# motadora.net
KiCad netlist of a schematic drawn in EAGLE
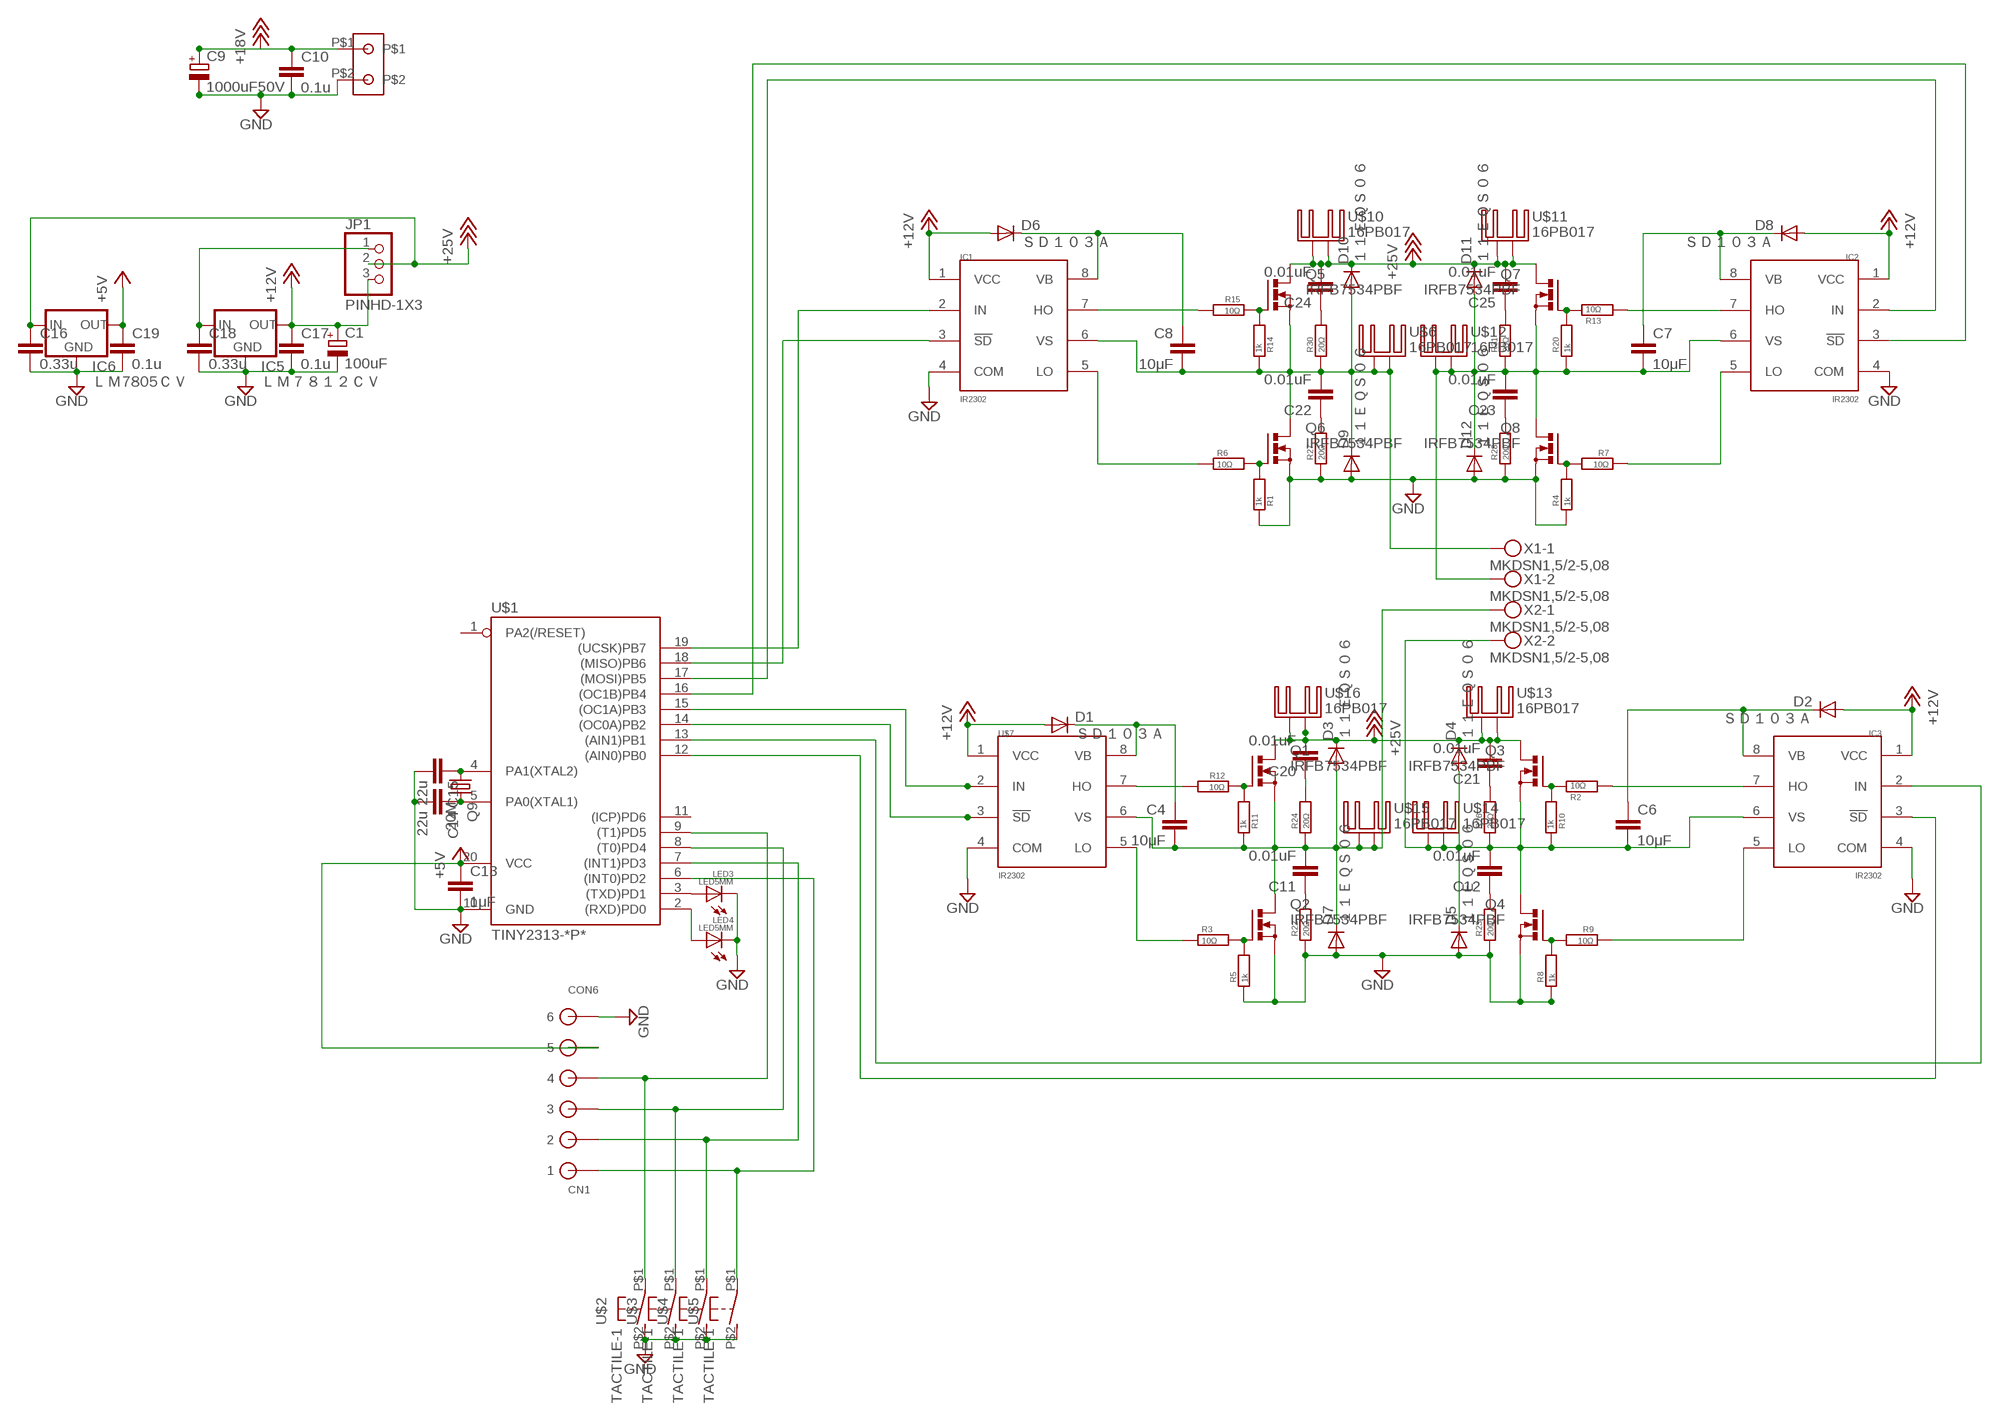
[diagram p0: schematic, sheet 1]

(export (version "E")
  (design (tool "Eeschema 10.0.6"))
  (components
    (comp (ref "C1")
      (value "100uF")
      (footprint "eagle-import:TT2D6")
      (libsource (lib "eagle-import") (part "CPOL-EUTT2D6"))
    )
    (comp (ref "C4")
      (value "10μF")
      (footprint "eagle-import:C025-025X050")
      (libsource (lib "eagle-import") (part "C-EU025-025X050"))
    )
    (comp (ref "C6")
      (value "10μF")
      (footprint "eagle-import:C025-025X050")
      (libsource (lib "eagle-import") (part "C-EU025-025X050"))
    )
    (comp (ref "C7")
      (value "10μF")
      (footprint "eagle-import:C025-025X050")
      (libsource (lib "eagle-import") (part "C-EU025-025X050"))
    )
    (comp (ref "C8")
      (value "10μF")
      (footprint "eagle-import:C025-025X050")
      (libsource (lib "eagle-import") (part "C-EU025-025X050"))
    )
    (comp (ref "C9")
      (value "1000uF50V")
      (footprint "eagle-import:E5-13")
      (libsource (lib "eagle-import") (part "CPOL-EUE5-13"))
    )
    (comp (ref "C10")
      (value "0.1u")
      (footprint "eagle-import:C5B3")
      (libsource (lib "eagle-import") (part "C5/3"))
    )
    (comp (ref "C11")
      (value "0.01uF")
      (footprint "eagle-import:C025-024X044")
      (libsource (lib "eagle-import") (part "_resistor(抵抗)_C-EU025-024X044"))
    )
    (comp (ref "C12")
      (value "0.01uF")
      (footprint "eagle-import:C025-024X044")
      (libsource (lib "eagle-import") (part "_resistor(抵抗)_C-EU025-024X044"))
    )
    (comp (ref "C13")
      (value "1μF")
      (footprint "eagle-import:C050-025X075")
      (libsource (lib "eagle-import") (part "_resistor(抵抗)_C-EU050-025X075"))
    )
    (comp (ref "C14")
      (value "22u")
      (footprint "eagle-import:C025-024X044")
      (libsource (lib "eagle-import") (part "C-EU025-024X044"))
    )
    (comp (ref "C15")
      (value "22u")
      (footprint "eagle-import:C025-024X044")
      (libsource (lib "eagle-import") (part "C-EU025-024X044"))
    )
    (comp (ref "C16")
      (value "0.33u")
      (footprint "eagle-import:C025-025X050")
      (libsource (lib "eagle-import") (part "_resistor(抵抗)_C-EU025-025X050"))
    )
    (comp (ref "C17")
      (value "0.1u")
      (footprint "eagle-import:C025-025X050")
      (libsource (lib "eagle-import") (part "_resistor(抵抗)_C-EU025-025X050"))
    )
    (comp (ref "C18")
      (value "0.33u")
      (footprint "eagle-import:C025-025X050")
      (libsource (lib "eagle-import") (part "_resistor(抵抗)_C-EU025-025X050"))
    )
    (comp (ref "C19")
      (value "0.1u")
      (footprint "eagle-import:C025-025X050")
      (libsource (lib "eagle-import") (part "_resistor(抵抗)_C-EU025-025X050"))
    )
    (comp (ref "C20")
      (value "0.01uF")
      (footprint "eagle-import:C025-024X044")
      (libsource (lib "eagle-import") (part "_resistor(抵抗)_C-EU025-024X044"))
    )
    (comp (ref "C21")
      (value "0.01uF")
      (footprint "eagle-import:C025-024X044")
      (libsource (lib "eagle-import") (part "_resistor(抵抗)_C-EU025-024X044"))
    )
    (comp (ref "C22")
      (value "0.01uF")
      (footprint "eagle-import:C025-024X044")
      (libsource (lib "eagle-import") (part "_resistor(抵抗)_C-EU025-024X044"))
    )
    (comp (ref "C23")
      (value "0.01uF")
      (footprint "eagle-import:C025-024X044")
      (libsource (lib "eagle-import") (part "_resistor(抵抗)_C-EU025-024X044"))
    )
    (comp (ref "C24")
      (value "0.01uF")
      (footprint "eagle-import:C025-024X044")
      (libsource (lib "eagle-import") (part "_resistor(抵抗)_C-EU025-024X044"))
    )
    (comp (ref "C25")
      (value "0.01uF")
      (footprint "eagle-import:C025-024X044")
      (libsource (lib "eagle-import") (part "_resistor(抵抗)_C-EU025-024X044"))
    )
    (comp (ref "CN1")
      (value "CON6")
      (footprint "eagle-import:CON6")
      (libsource (lib "eagle-import") (part "CON6"))
    )
    (comp (ref "D1")
      (value "ＳＤ１０３Ａ")
      (footprint "eagle-import:D-5")
      (libsource (lib "eagle-import") (part "DIODE-D-5"))
    )
    (comp (ref "D2")
      (value "ＳＤ１０３Ａ")
      (footprint "eagle-import:D-5")
      (libsource (lib "eagle-import") (part "DIODE-D-5"))
    )
    (comp (ref "D3")
      (value "１１ＥＱＳ０６")
      (footprint "eagle-import:D-5")
      (libsource (lib "eagle-import") (part "DIODE-D-5"))
    )
    (comp (ref "D4")
      (value "１１ＥＱＳ０６")
      (footprint "eagle-import:D-5")
      (libsource (lib "eagle-import") (part "DIODE-D-5"))
    )
    (comp (ref "D5")
      (value "１１ＥＱＳ０６")
      (footprint "eagle-import:D-5")
      (libsource (lib "eagle-import") (part "DIODE-D-5"))
    )
    (comp (ref "D6")
      (value "ＳＤ１０３Ａ")
      (footprint "eagle-import:D-5")
      (libsource (lib "eagle-import") (part "DIODE-D-5"))
    )
    (comp (ref "D7")
      (value "１１ＥＱＳ０６")
      (footprint "eagle-import:D-5")
      (libsource (lib "eagle-import") (part "DIODE-D-5"))
    )
    (comp (ref "D8")
      (value "ＳＤ１０３Ａ")
      (footprint "eagle-import:D-5")
      (libsource (lib "eagle-import") (part "DIODE-D-5"))
    )
    (comp (ref "D9")
      (value "１１ＥＱＳ０６")
      (footprint "eagle-import:D-5")
      (libsource (lib "eagle-import") (part "DIODE-D-5"))
    )
    (comp (ref "D10")
      (value "１１ＥＱＳ０６")
      (footprint "eagle-import:D-5")
      (libsource (lib "eagle-import") (part "DIODE-D-5"))
    )
    (comp (ref "D11")
      (value "１１ＥＱＳ０６")
      (footprint "eagle-import:D-5")
      (libsource (lib "eagle-import") (part "DIODE-D-5"))
    )
    (comp (ref "D12")
      (value "１１ＥＱＳ０６")
      (footprint "eagle-import:D-5")
      (libsource (lib "eagle-import") (part "DIODE-D-5"))
    )
    (comp (ref "IC1")
      (value "IR2302")
      (footprint "eagle-import:DIL08")
      (libsource (lib "eagle-import") (part "IR2302IR2302"))
    )
    (comp (ref "IC2")
      (value "IR2302")
      (footprint "eagle-import:DIL08")
      (libsource (lib "eagle-import") (part "IR2302IR2302"))
    )
    (comp (ref "IC3")
      (value "IR2302")
      (footprint "eagle-import:DIL08")
      (libsource (lib "eagle-import") (part "IR2302IR2302"))
    )
    (comp (ref "IC5")
      (value "ＬＭ７８１２ＣＶ")
      (footprint "eagle-import:78XXS")
      (libsource (lib "eagle-import") (part "78XXS"))
    )
    (comp (ref "IC6")
      (value "ＬＭ7805ＣＶ")
      (footprint "eagle-import:78XXS")
      (libsource (lib "eagle-import") (part "78XXS"))
    )
    (comp (ref "JP1")
      (value "PINHD-1X3")
      (footprint "eagle-import:1X03")
      (libsource (lib "eagle-import") (part "PINHD-1X3"))
    )
    (comp (ref "LED3")
      (value "LED5MM")
      (footprint "eagle-import:LED5MM")
      (libsource (lib "eagle-import") (part "LED5MM"))
    )
    (comp (ref "LED4")
      (value "LED5MM")
      (footprint "eagle-import:LED5MM")
      (libsource (lib "eagle-import") (part "LED5MM"))
    )
    (comp (ref "Q1")
      (value "IRFB7534PBF")
      (footprint "eagle-import:TO220BV")
      (libsource (lib "eagle-import") (part "BUZ11BV"))
    )
    (comp (ref "Q2")
      (value "IRFB7534PBF")
      (footprint "eagle-import:TO220BV")
      (libsource (lib "eagle-import") (part "BUZ11BV"))
    )
    (comp (ref "Q3")
      (value "IRFB7534PBF")
      (footprint "eagle-import:TO220BV")
      (libsource (lib "eagle-import") (part "BUZ11BV"))
    )
    (comp (ref "Q4")
      (value "IRFB7534PBF")
      (footprint "eagle-import:TO220BV")
      (libsource (lib "eagle-import") (part "BUZ11BV"))
    )
    (comp (ref "Q5")
      (value "IRFB7534PBF")
      (footprint "eagle-import:TO220BV")
      (libsource (lib "eagle-import") (part "BUZ11BV"))
    )
    (comp (ref "Q6")
      (value "IRFB7534PBF")
      (footprint "eagle-import:TO220BV")
      (libsource (lib "eagle-import") (part "BUZ11BV"))
    )
    (comp (ref "Q7")
      (value "IRFB7534PBF")
      (footprint "eagle-import:TO220BV")
      (libsource (lib "eagle-import") (part "BUZ11BV"))
    )
    (comp (ref "Q8")
      (value "IRFB7534PBF")
      (footprint "eagle-import:TO220BV")
      (libsource (lib "eagle-import") (part "BUZ11BV"))
    )
    (comp (ref "Q9")
      (value "20M")
      (footprint "eagle-import:HC49_S")
      (libsource (lib "eagle-import") (part "CRYSTALHC49S"))
    )
    (comp (ref "R1")
      (value "1k")
      (footprint "eagle-import:0207_7")
      (libsource (lib "eagle-import") (part "R-EU_0207/7"))
    )
    (comp (ref "R2")
      (value "10Ω")
      (footprint "eagle-import:1_4W(2.5MM)_")
      (libsource (lib "eagle-import") (part "R-EU_1/4W(2.5MM)"))
    )
    (comp (ref "R3")
      (value "10Ω")
      (footprint "eagle-import:0207_10")
      (libsource (lib "eagle-import") (part "R-EU_0207/10"))
    )
    (comp (ref "R4")
      (value "1k")
      (footprint "eagle-import:0207_7")
      (libsource (lib "eagle-import") (part "R-EU_0207/7"))
    )
    (comp (ref "R5")
      (value "1k")
      (footprint "eagle-import:0207_7")
      (libsource (lib "eagle-import") (part "R-EU_0207/7"))
    )
    (comp (ref "R6")
      (value "10Ω")
      (footprint "eagle-import:0207_10")
      (libsource (lib "eagle-import") (part "R-EU_0207/10"))
    )
    (comp (ref "R7")
      (value "10Ω")
      (footprint "eagle-import:0207_10")
      (libsource (lib "eagle-import") (part "R-EU_0207/10"))
    )
    (comp (ref "R8")
      (value "1k")
      (footprint "eagle-import:0207_7")
      (libsource (lib "eagle-import") (part "R-EU_0207/7"))
    )
    (comp (ref "R9")
      (value "10Ω")
      (footprint "eagle-import:0207_10")
      (libsource (lib "eagle-import") (part "R-EU_0207/10"))
    )
    (comp (ref "R10")
      (value "1k")
      (footprint "eagle-import:1_4W(2.5MM)_")
      (libsource (lib "eagle-import") (part "R-EU_1/4W(2.5MM)"))
    )
    (comp (ref "R11")
      (value "1k")
      (footprint "eagle-import:1_4W(2.5MM)_")
      (libsource (lib "eagle-import") (part "R-EU_1/4W(2.5MM)"))
    )
    (comp (ref "R12")
      (value "10Ω")
      (footprint "eagle-import:1_4W(2.5MM)_")
      (libsource (lib "eagle-import") (part "R-EU_1/4W(2.5MM)"))
    )
    (comp (ref "R13")
      (value "10Ω")
      (footprint "eagle-import:1_4W(2.5MM)_")
      (libsource (lib "eagle-import") (part "R-EU_1/4W(2.5MM)"))
    )
    (comp (ref "R14")
      (value "1k")
      (footprint "eagle-import:1_4W(2.5MM)_")
      (libsource (lib "eagle-import") (part "R-EU_1/4W(2.5MM)"))
    )
    (comp (ref "R15")
      (value "10Ω")
      (footprint "eagle-import:1_4W(2.5MM)_")
      (libsource (lib "eagle-import") (part "R-EU_1/4W(2.5MM)"))
    )
    (comp (ref "R20")
      (value "1k")
      (footprint "eagle-import:1_4W(2.5MM)_")
      (libsource (lib "eagle-import") (part "R-EU_1/4W(2.5MM)"))
    )
    (comp (ref "R22")
      (value "20Ω")
      (footprint "eagle-import:0207_2V")
      (libsource (lib "eagle-import") (part "R-EU_0207/2V"))
    )
    (comp (ref "R23")
      (value "20Ω")
      (footprint "eagle-import:0207_2V")
      (libsource (lib "eagle-import") (part "R-EU_0207/2V"))
    )
    (comp (ref "R24")
      (value "20Ω")
      (footprint "eagle-import:0207_2V")
      (libsource (lib "eagle-import") (part "R-EU_0207/2V"))
    )
    (comp (ref "R26")
      (value "20Ω")
      (footprint "eagle-import:0207_2V")
      (libsource (lib "eagle-import") (part "R-EU_0207/2V"))
    )
    (comp (ref "R27")
      (value "20Ω")
      (footprint "eagle-import:0207_2V")
      (libsource (lib "eagle-import") (part "R-EU_0207/2V"))
    )
    (comp (ref "R28")
      (value "20Ω")
      (footprint "eagle-import:0207_2V")
      (libsource (lib "eagle-import") (part "R-EU_0207/2V"))
    )
    (comp (ref "R30")
      (value "20Ω")
      (footprint "eagle-import:1_4W(2.5MM)_")
      (libsource (lib "eagle-import") (part "R-EU_1/4W(2.5MM)"))
    )
    (comp (ref "R31")
      (value "20Ω")
      (footprint "eagle-import:0207_2V")
      (libsource (lib "eagle-import") (part "R-EU_0207/2V"))
    )
    (comp (ref "T2")
      (value "TANSIDAI")
      (footprint "eagle-import:A")
      (libsource (lib "eagle-import") (part "TANSIDAI"))
    )
    (comp (ref "U$1")
      (value "TINY2313-*P*")
      (footprint "eagle-import:DIL20")
      (libsource (lib "eagle-import") (part "TINY2313-P"))
    )
    (comp (ref "U$2")
      (value "TACTILE-1")
      (footprint "eagle-import:TACTILE")
      (libsource (lib "eagle-import") (part "TACTILE-1"))
    )
    (comp (ref "U$3")
      (value "TACTILE-1")
      (footprint "eagle-import:TACTILE")
      (libsource (lib "eagle-import") (part "TACTILE-1"))
    )
    (comp (ref "U$4")
      (value "TACTILE-1")
      (footprint "eagle-import:TACTILE")
      (libsource (lib "eagle-import") (part "TACTILE-1"))
    )
    (comp (ref "U$5")
      (value "TACTILE-1")
      (footprint "eagle-import:TACTILE")
      (libsource (lib "eagle-import") (part "TACTILE-1"))
    )
    (comp (ref "U$6")
      (value "16PB017")
      (footprint "eagle-import:16PB017")
      (libsource (lib "eagle-import") (part "16PB017"))
    )
    (comp (ref "U$7")
      (value "IR2302")
      (footprint "eagle-import:DIL08")
      (libsource (lib "eagle-import") (part "IR2302IR2302"))
    )
    (comp (ref "U$10")
      (value "16PB017")
      (footprint "eagle-import:16PB017")
      (libsource (lib "eagle-import") (part "16PB017"))
    )
    (comp (ref "U$11")
      (value "16PB017")
      (footprint "eagle-import:16PB017")
      (libsource (lib "eagle-import") (part "16PB017"))
    )
    (comp (ref "U$12")
      (value "16PB017")
      (footprint "eagle-import:16PB017")
      (libsource (lib "eagle-import") (part "16PB017"))
    )
    (comp (ref "U$13")
      (value "16PB017")
      (footprint "eagle-import:16PB017")
      (libsource (lib "eagle-import") (part "16PB017"))
    )
    (comp (ref "U$14")
      (value "16PB017")
      (footprint "eagle-import:16PB017")
      (libsource (lib "eagle-import") (part "16PB017"))
    )
    (comp (ref "U$15")
      (value "16PB017")
      (footprint "eagle-import:16PB017")
      (libsource (lib "eagle-import") (part "16PB017"))
    )
    (comp (ref "U$16")
      (value "16PB017")
      (footprint "eagle-import:16PB017")
      (libsource (lib "eagle-import") (part "16PB017"))
    )
    (comp (ref "X1")
      (value "MKDSN1,5/2-5,08")
      (footprint "eagle-import:MKDSN1,5_2-5,08")
      (fields (field (name "MPN") "MKDSN 1,5/2-5.08"))
      (libsource (lib "eagle-import") (part "MKDSN1,5/2-5,08"))
    )
    (comp (ref "X2")
      (value "MKDSN1,5/2-5,08")
      (footprint "eagle-import:MKDSN1,5_2-5,08")
      (fields (field (name "MPN") "MKDSN 1,5/2-5.08"))
      (libsource (lib "eagle-import") (part "MKDSN1,5/2-5,08"))
    )
  )
  (nets
    (net (code "1") (name "+5V") (class "Default")
      (node (ref "C13") (pin "1") (pinfunction "1_1") (pintype "passive"))
      (node (ref "C19") (pin "1") (pinfunction "1_1") (pintype "passive"))
      (node (ref "CN1") (pin "P$5") (pinfunction "5_P$5") (pintype "bidirectional"))
      (node (ref "IC6") (pin "OUT") (pinfunction "OUT_OUT") (pintype "passive"))
      (node (ref "U$1") (pin "20") (pinfunction "VCC_20") (pintype "power_in"))
    )
    (net (code "2") (name "+12V") (class "Default")
      (node (ref "C1") (pin "+") (pinfunction "+_+") (pintype "passive"))
      (node (ref "C17") (pin "1") (pinfunction "1_1") (pintype "passive"))
      (node (ref "D1") (pin "A") (pinfunction "A_A") (pintype "passive"))
      (node (ref "D2") (pin "A") (pinfunction "A_A") (pintype "passive"))
      (node (ref "D6") (pin "A") (pinfunction "A_A") (pintype "passive"))
      (node (ref "D8") (pin "A") (pinfunction "A_A") (pintype "passive"))
      (node (ref "IC1") (pin "1") (pinfunction "VCC_1") (pintype "bidirectional"))
      (node (ref "IC2") (pin "1") (pinfunction "VCC_1") (pintype "bidirectional"))
      (node (ref "IC3") (pin "1") (pinfunction "VCC_1") (pintype "bidirectional"))
      (node (ref "IC5") (pin "OUT") (pinfunction "OUT_OUT") (pintype "passive"))
      (node (ref "JP1") (pin "3") (pinfunction "3_3") (pintype "passive"))
      (node (ref "U$7") (pin "1") (pinfunction "VCC_1") (pintype "bidirectional"))
    )
    (net (code "3") (name "+18V") (class "Default")
      (node (ref "C10") (pin "1") (pinfunction "1_1") (pintype "passive"))
      (node (ref "C16") (pin "1") (pinfunction "1_1") (pintype "passive"))
      (node (ref "C20") (pin "2") (pinfunction "2_2") (pintype "passive"))
      (node (ref "C21") (pin "2") (pinfunction "2_2") (pintype "passive"))
      (node (ref "C24") (pin "2") (pinfunction "2_2") (pintype "passive"))
      (node (ref "C25") (pin "2") (pinfunction "2_2") (pintype "passive"))
      (node (ref "C9") (pin "+") (pinfunction "+_+") (pintype "passive"))
      (node (ref "D10") (pin "C") (pinfunction "C_C") (pintype "passive"))
      (node (ref "D11") (pin "C") (pinfunction "C_C") (pintype "passive"))
      (node (ref "D3") (pin "C") (pinfunction "C_C") (pintype "passive"))
      (node (ref "D4") (pin "C") (pinfunction "C_C") (pintype "passive"))
      (node (ref "IC6") (pin "IN") (pinfunction "IN_IN") (pintype "input"))
      (node (ref "JP1") (pin "2") (pinfunction "2_2") (pintype "passive"))
      (node (ref "Q1") (pin "D") (pinfunction "D_D") (pintype "passive"))
      (node (ref "Q3") (pin "D") (pinfunction "D_D") (pintype "passive"))
      (node (ref "Q5") (pin "D") (pinfunction "D_D") (pintype "passive"))
      (node (ref "Q7") (pin "D") (pinfunction "D_D") (pintype "passive"))
      (node (ref "T2") (pin "P$1") (pinfunction "P$1_P$1") (pintype "bidirectional"))
      (node (ref "U$10") (pin "P$1") (pinfunction "K_P$1") (pintype "passive"))
      (node (ref "U$10") (pin "P$2") (pinfunction "K_P$2") (pintype "passive"))
      (node (ref "U$11") (pin "P$1") (pinfunction "K_P$1") (pintype "passive"))
      (node (ref "U$11") (pin "P$2") (pinfunction "K_P$2") (pintype "passive"))
      (node (ref "U$13") (pin "P$1") (pinfunction "K_P$1") (pintype "passive"))
      (node (ref "U$13") (pin "P$2") (pinfunction "K_P$2") (pintype "passive"))
      (node (ref "U$16") (pin "P$1") (pinfunction "K_P$1") (pintype "passive"))
      (node (ref "U$16") (pin "P$2") (pinfunction "K_P$2") (pintype "passive"))
    )
    (net (code "4") (name "GND") (class "Default")
      (node (ref "C1") (pin "-") (pinfunction "-_-") (pintype "passive"))
      (node (ref "C10") (pin "2") (pinfunction "2_2") (pintype "passive"))
      (node (ref "C13") (pin "2") (pinfunction "2_2") (pintype "passive"))
      (node (ref "C14") (pin "2") (pinfunction "2_2") (pintype "passive"))
      (node (ref "C15") (pin "2") (pinfunction "2_2") (pintype "passive"))
      (node (ref "C16") (pin "2") (pinfunction "2_2") (pintype "passive"))
      (node (ref "C17") (pin "2") (pinfunction "2_2") (pintype "passive"))
      (node (ref "C18") (pin "2") (pinfunction "2_2") (pintype "passive"))
      (node (ref "C19") (pin "2") (pinfunction "2_2") (pintype "passive"))
      (node (ref "C9") (pin "-") (pinfunction "-_-") (pintype "passive"))
      (node (ref "CN1") (pin "P$6") (pinfunction "6_P$6") (pintype "bidirectional"))
      (node (ref "D12") (pin "A") (pinfunction "A_A") (pintype "passive"))
      (node (ref "D5") (pin "A") (pinfunction "A_A") (pintype "passive"))
      (node (ref "D7") (pin "A") (pinfunction "A_A") (pintype "passive"))
      (node (ref "D9") (pin "A") (pinfunction "A_A") (pintype "passive"))
      (node (ref "IC1") (pin "4") (pinfunction "COM_4") (pintype "bidirectional"))
      (node (ref "IC2") (pin "4") (pinfunction "COM_4") (pintype "bidirectional"))
      (node (ref "IC3") (pin "4") (pinfunction "COM_4") (pintype "bidirectional"))
      (node (ref "IC5") (pin "GND") (pinfunction "GND_GND") (pintype "input"))
      (node (ref "IC6") (pin "GND") (pinfunction "GND_GND") (pintype "input"))
      (node (ref "LED3") (pin "K") (pinfunction "C_K") (pintype "passive"))
      (node (ref "LED4") (pin "K") (pinfunction "C_K") (pintype "passive"))
      (node (ref "Q2") (pin "S") (pinfunction "S_S") (pintype "passive"))
      (node (ref "Q4") (pin "S") (pinfunction "S_S") (pintype "passive"))
      (node (ref "Q6") (pin "S") (pinfunction "S_S") (pintype "passive"))
      (node (ref "Q8") (pin "S") (pinfunction "S_S") (pintype "passive"))
      (node (ref "R1") (pin "1") (pinfunction "1_1") (pintype "passive"))
      (node (ref "R22") (pin "1") (pinfunction "1_1") (pintype "passive"))
      (node (ref "R23") (pin "1") (pinfunction "1_1") (pintype "passive"))
      (node (ref "R27") (pin "1") (pinfunction "1_1") (pintype "passive"))
      (node (ref "R28") (pin "1") (pinfunction "1_1") (pintype "passive"))
      (node (ref "R4") (pin "1") (pinfunction "1_1") (pintype "passive"))
      (node (ref "R5") (pin "1") (pinfunction "1_1") (pintype "passive"))
      (node (ref "R8") (pin "1") (pinfunction "1_1") (pintype "passive"))
      (node (ref "T2") (pin "P$2") (pinfunction "P$2_P$2") (pintype "bidirectional"))
      (node (ref "U$1") (pin "10") (pinfunction "GND_10") (pintype "power_in"))
      (node (ref "U$2") (pin "P$2") (pinfunction "S_P$2") (pintype "passive"))
      (node (ref "U$3") (pin "P$2") (pinfunction "S_P$2") (pintype "passive"))
      (node (ref "U$4") (pin "P$2") (pinfunction "S_P$2") (pintype "passive"))
      (node (ref "U$5") (pin "P$2") (pinfunction "S_P$2") (pintype "passive"))
      (node (ref "U$7") (pin "4") (pinfunction "COM_4") (pintype "bidirectional"))
    )
    (net (code "5") (name "Net-(C11-Pad1)") (class "Default")
      (node (ref "C11") (pin "1") (pinfunction "1_1") (pintype "passive"))
      (node (ref "R22") (pin "2") (pinfunction "2_2") (pintype "passive"))
    )
    (net (code "6") (name "Net-(C12-Pad1)") (class "Default")
      (node (ref "C12") (pin "1") (pinfunction "1_1") (pintype "passive"))
      (node (ref "R23") (pin "2") (pinfunction "2_2") (pintype "passive"))
    )
    (net (code "7") (name "Net-(C18-Pad1)") (class "Default")
      (node (ref "C18") (pin "1") (pinfunction "1_1") (pintype "passive"))
      (node (ref "IC5") (pin "IN") (pinfunction "IN_IN") (pintype "input"))
      (node (ref "JP1") (pin "1") (pinfunction "1_1") (pintype "passive"))
    )
    (net (code "8") (name "Net-(C20-Pad1)") (class "Default")
      (node (ref "C20") (pin "1") (pinfunction "1_1") (pintype "passive"))
      (node (ref "R24") (pin "2") (pinfunction "2_2") (pintype "passive"))
    )
    (net (code "9") (name "Net-(C21-Pad1)") (class "Default")
      (node (ref "C21") (pin "1") (pinfunction "1_1") (pintype "passive"))
      (node (ref "R26") (pin "2") (pinfunction "2_2") (pintype "passive"))
    )
    (net (code "10") (name "Net-(C22-Pad1)") (class "Default")
      (node (ref "C22") (pin "1") (pinfunction "1_1") (pintype "passive"))
      (node (ref "R27") (pin "2") (pinfunction "2_2") (pintype "passive"))
    )
    (net (code "11") (name "Net-(C23-Pad1)") (class "Default")
      (node (ref "C23") (pin "1") (pinfunction "1_1") (pintype "passive"))
      (node (ref "R28") (pin "2") (pinfunction "2_2") (pintype "passive"))
    )
    (net (code "12") (name "Net-(C25-Pad1)") (class "Default")
      (node (ref "C25") (pin "1") (pinfunction "1_1") (pintype "passive"))
      (node (ref "R31") (pin "2") (pinfunction "2_2") (pintype "passive"))
    )
    (net (code "13") (name "Net-(CN1-1)") (class "Default")
      (node (ref "CN1") (pin "P$1") (pinfunction "1_P$1") (pintype "bidirectional"))
      (node (ref "U$1") (pin "6") (pinfunction "(INT0)PD2_6") (pintype "bidirectional"))
      (node (ref "U$5") (pin "P$1") (pinfunction "P_P$1") (pintype "passive"))
    )
    (net (code "14") (name "Net-(CN1-2)") (class "Default")
      (node (ref "CN1") (pin "P$2") (pinfunction "2_P$2") (pintype "bidirectional"))
      (node (ref "U$1") (pin "7") (pinfunction "(INT1)PD3_7") (pintype "bidirectional"))
      (node (ref "U$4") (pin "P$1") (pinfunction "P_P$1") (pintype "passive"))
    )
    (net (code "15") (name "Net-(CN1-3)") (class "Default")
      (node (ref "CN1") (pin "P$3") (pinfunction "3_P$3") (pintype "bidirectional"))
      (node (ref "U$1") (pin "8") (pinfunction "(T0)PD4_8") (pintype "bidirectional"))
      (node (ref "U$3") (pin "P$1") (pinfunction "P_P$1") (pintype "passive"))
    )
    (net (code "16") (name "Net-(CN1-4)") (class "Default")
      (node (ref "CN1") (pin "P$4") (pinfunction "4_P$4") (pintype "bidirectional"))
      (node (ref "U$1") (pin "9") (pinfunction "(T1)PD5_9") (pintype "bidirectional"))
      (node (ref "U$2") (pin "P$1") (pinfunction "P_P$1") (pintype "passive"))
    )
    (net (code "17") (name "Net-(IC1-HO)") (class "Default")
      (node (ref "IC1") (pin "7") (pinfunction "HO_7") (pintype "bidirectional"))
      (node (ref "R15") (pin "4") (pinfunction "2_4") (pintype "passive"))
    )
    (net (code "18") (name "Net-(IC1-IN)") (class "Default")
      (node (ref "IC1") (pin "2") (pinfunction "IN_2") (pintype "bidirectional"))
      (node (ref "U$1") (pin "19") (pinfunction "(UCSK)PB7_19") (pintype "bidirectional"))
    )
    (net (code "19") (name "Net-(IC1-LO)") (class "Default")
      (node (ref "IC1") (pin "5") (pinfunction "LO_5") (pintype "bidirectional"))
      (node (ref "R6") (pin "1") (pinfunction "1_1") (pintype "passive"))
    )
    (net (code "20") (name "Net-(IC1-VB)") (class "Default")
      (node (ref "C8") (pin "1") (pinfunction "1_1") (pintype "passive"))
      (node (ref "D6") (pin "C") (pinfunction "C_C") (pintype "passive"))
      (node (ref "IC1") (pin "8") (pinfunction "VB_8") (pintype "bidirectional"))
    )
    (net (code "21") (name "Net-(IC1-VS)") (class "Default")
      (node (ref "C22") (pin "2") (pinfunction "2_2") (pintype "passive"))
      (node (ref "C8") (pin "2") (pinfunction "2_2") (pintype "passive"))
      (node (ref "D10") (pin "A") (pinfunction "A_A") (pintype "passive"))
      (node (ref "D9") (pin "C") (pinfunction "C_C") (pintype "passive"))
      (node (ref "IC1") (pin "6") (pinfunction "VS_6") (pintype "bidirectional"))
      (node (ref "Q5") (pin "S") (pinfunction "S_S") (pintype "passive"))
      (node (ref "Q6") (pin "D") (pinfunction "D_D") (pintype "passive"))
      (node (ref "R14") (pin "3") (pinfunction "1_3") (pintype "passive"))
      (node (ref "R30") (pin "3") (pinfunction "1_3") (pintype "passive"))
      (node (ref "U$6") (pin "P$1") (pinfunction "K_P$1") (pintype "passive"))
      (node (ref "U$6") (pin "P$2") (pinfunction "K_P$2") (pintype "passive"))
      (node (ref "X1") (pin "1") (pinfunction "KL_1") (pintype "passive"))
    )
    (net (code "22") (name "Net-(IC1-~{SD})") (class "Default")
      (node (ref "IC1") (pin "3") (pinfunction "~{SD}_3") (pintype "bidirectional"))
      (node (ref "U$1") (pin "18") (pinfunction "(MISO)PB6_18") (pintype "bidirectional"))
    )
    (net (code "23") (name "Net-(IC2-HO)") (class "Default")
      (node (ref "IC2") (pin "7") (pinfunction "HO_7") (pintype "bidirectional"))
      (node (ref "R13") (pin "4") (pinfunction "2_4") (pintype "passive"))
    )
    (net (code "24") (name "Net-(IC2-IN)") (class "Default")
      (node (ref "IC2") (pin "2") (pinfunction "IN_2") (pintype "bidirectional"))
      (node (ref "U$1") (pin "17") (pinfunction "(MOSI)PB5_17") (pintype "bidirectional"))
    )
    (net (code "25") (name "Net-(IC2-LO)") (class "Default")
      (node (ref "IC2") (pin "5") (pinfunction "LO_5") (pintype "bidirectional"))
      (node (ref "R7") (pin "1") (pinfunction "1_1") (pintype "passive"))
    )
    (net (code "26") (name "Net-(IC2-VB)") (class "Default")
      (node (ref "C7") (pin "1") (pinfunction "1_1") (pintype "passive"))
      (node (ref "D8") (pin "C") (pinfunction "C_C") (pintype "passive"))
      (node (ref "IC2") (pin "8") (pinfunction "VB_8") (pintype "bidirectional"))
    )
    (net (code "27") (name "Net-(IC2-VS)") (class "Default")
      (node (ref "C23") (pin "2") (pinfunction "2_2") (pintype "passive"))
      (node (ref "C7") (pin "2") (pinfunction "2_2") (pintype "passive"))
      (node (ref "D11") (pin "A") (pinfunction "A_A") (pintype "passive"))
      (node (ref "D12") (pin "C") (pinfunction "C_C") (pintype "passive"))
      (node (ref "IC2") (pin "6") (pinfunction "VS_6") (pintype "bidirectional"))
      (node (ref "Q7") (pin "S") (pinfunction "S_S") (pintype "passive"))
      (node (ref "Q8") (pin "D") (pinfunction "D_D") (pintype "passive"))
      (node (ref "R20") (pin "3") (pinfunction "1_3") (pintype "passive"))
      (node (ref "R31") (pin "1") (pinfunction "1_1") (pintype "passive"))
      (node (ref "U$12") (pin "P$1") (pinfunction "K_P$1") (pintype "passive"))
      (node (ref "U$12") (pin "P$2") (pinfunction "K_P$2") (pintype "passive"))
      (node (ref "X1") (pin "2") (pinfunction "KL_2") (pintype "passive"))
    )
    (net (code "28") (name "Net-(IC2-~{SD})") (class "Default")
      (node (ref "IC2") (pin "3") (pinfunction "~{SD}_3") (pintype "bidirectional"))
      (node (ref "U$1") (pin "16") (pinfunction "(OC1B)PB4_16") (pintype "bidirectional"))
    )
    (net (code "29") (name "Net-(IC3-HO)") (class "Default")
      (node (ref "IC3") (pin "7") (pinfunction "HO_7") (pintype "bidirectional"))
      (node (ref "R2") (pin "4") (pinfunction "2_4") (pintype "passive"))
    )
    (net (code "30") (name "Net-(IC3-IN)") (class "Default")
      (node (ref "IC3") (pin "2") (pinfunction "IN_2") (pintype "bidirectional"))
      (node (ref "U$1") (pin "13") (pinfunction "(AIN1)PB1_13") (pintype "bidirectional"))
    )
    (net (code "31") (name "Net-(IC3-LO)") (class "Default")
      (node (ref "IC3") (pin "5") (pinfunction "LO_5") (pintype "bidirectional"))
      (node (ref "R9") (pin "1") (pinfunction "1_1") (pintype "passive"))
    )
    (net (code "32") (name "Net-(IC3-VB)") (class "Default")
      (node (ref "C6") (pin "1") (pinfunction "1_1") (pintype "passive"))
      (node (ref "D2") (pin "C") (pinfunction "C_C") (pintype "passive"))
      (node (ref "IC3") (pin "8") (pinfunction "VB_8") (pintype "bidirectional"))
    )
    (net (code "33") (name "Net-(IC3-VS)") (class "Default")
      (node (ref "C12") (pin "2") (pinfunction "2_2") (pintype "passive"))
      (node (ref "C6") (pin "2") (pinfunction "2_2") (pintype "passive"))
      (node (ref "D4") (pin "A") (pinfunction "A_A") (pintype "passive"))
      (node (ref "D5") (pin "C") (pinfunction "C_C") (pintype "passive"))
      (node (ref "IC3") (pin "6") (pinfunction "VS_6") (pintype "bidirectional"))
      (node (ref "Q3") (pin "S") (pinfunction "S_S") (pintype "passive"))
      (node (ref "Q4") (pin "D") (pinfunction "D_D") (pintype "passive"))
      (node (ref "R10") (pin "3") (pinfunction "1_3") (pintype "passive"))
      (node (ref "R26") (pin "1") (pinfunction "1_1") (pintype "passive"))
      (node (ref "U$14") (pin "P$1") (pinfunction "K_P$1") (pintype "passive"))
      (node (ref "U$14") (pin "P$2") (pinfunction "K_P$2") (pintype "passive"))
      (node (ref "X2") (pin "2") (pinfunction "KL_2") (pintype "passive"))
    )
    (net (code "34") (name "Net-(IC3-~{SD})") (class "Default")
      (node (ref "IC3") (pin "3") (pinfunction "~{SD}_3") (pintype "bidirectional"))
      (node (ref "U$1") (pin "12") (pinfunction "(AIN0)PB0_12") (pintype "bidirectional"))
    )
    (net (code "35") (name "Net-(Q2-PadG)") (class "Default")
      (node (ref "Q2") (pin "G") (pinfunction "G_G") (pintype "passive"))
      (node (ref "R3") (pin "2") (pinfunction "2_2") (pintype "passive"))
      (node (ref "R5") (pin "2") (pinfunction "2_2") (pintype "passive"))
    )
    (net (code "36") (name "Net-(Q4-PadG)") (class "Default")
      (node (ref "Q4") (pin "G") (pinfunction "G_G") (pintype "passive"))
      (node (ref "R8") (pin "2") (pinfunction "2_2") (pintype "passive"))
      (node (ref "R9") (pin "2") (pinfunction "2_2") (pintype "passive"))
    )
    (net (code "37") (name "Net-(Q6-PadG)") (class "Default")
      (node (ref "Q6") (pin "G") (pinfunction "G_G") (pintype "passive"))
      (node (ref "R1") (pin "2") (pinfunction "2_2") (pintype "passive"))
      (node (ref "R6") (pin "2") (pinfunction "2_2") (pintype "passive"))
    )
    (net (code "38") (name "Net-(Q8-PadG)") (class "Default")
      (node (ref "Q8") (pin "G") (pinfunction "G_G") (pintype "passive"))
      (node (ref "R4") (pin "2") (pinfunction "2_2") (pintype "passive"))
      (node (ref "R7") (pin "2") (pinfunction "2_2") (pintype "passive"))
    )
    (net (code "39") (name "Net-(R10-2)") (class "Default")
      (node (ref "Q3") (pin "G") (pinfunction "G_G") (pintype "passive"))
      (node (ref "R10") (pin "4") (pinfunction "2_4") (pintype "passive"))
      (node (ref "R2") (pin "3") (pinfunction "1_3") (pintype "passive"))
    )
    (net (code "40") (name "Net-(R11-1)") (class "Default")
      (node (ref "C11") (pin "2") (pinfunction "2_2") (pintype "passive"))
      (node (ref "C4") (pin "2") (pinfunction "2_2") (pintype "passive"))
      (node (ref "D3") (pin "A") (pinfunction "A_A") (pintype "passive"))
      (node (ref "D7") (pin "C") (pinfunction "C_C") (pintype "passive"))
      (node (ref "Q1") (pin "S") (pinfunction "S_S") (pintype "passive"))
      (node (ref "Q2") (pin "D") (pinfunction "D_D") (pintype "passive"))
      (node (ref "R11") (pin "3") (pinfunction "1_3") (pintype "passive"))
      (node (ref "R24") (pin "1") (pinfunction "1_1") (pintype "passive"))
      (node (ref "U$15") (pin "P$1") (pinfunction "K_P$1") (pintype "passive"))
      (node (ref "U$15") (pin "P$2") (pinfunction "K_P$2") (pintype "passive"))
      (node (ref "U$7") (pin "6") (pinfunction "VS_6") (pintype "bidirectional"))
      (node (ref "X2") (pin "1") (pinfunction "KL_1") (pintype "passive"))
    )
    (net (code "41") (name "Net-(R11-2)") (class "Default")
      (node (ref "Q1") (pin "G") (pinfunction "G_G") (pintype "passive"))
      (node (ref "R11") (pin "4") (pinfunction "2_4") (pintype "passive"))
      (node (ref "R12") (pin "3") (pinfunction "1_3") (pintype "passive"))
    )
    (net (code "42") (name "Net-(R12-2)") (class "Default")
      (node (ref "R12") (pin "4") (pinfunction "2_4") (pintype "passive"))
      (node (ref "U$7") (pin "7") (pinfunction "HO_7") (pintype "bidirectional"))
    )
    (net (code "43") (name "Net-(R13-1)") (class "Default")
      (node (ref "Q7") (pin "G") (pinfunction "G_G") (pintype "passive"))
      (node (ref "R13") (pin "3") (pinfunction "1_3") (pintype "passive"))
      (node (ref "R20") (pin "4") (pinfunction "2_4") (pintype "passive"))
    )
    (net (code "44") (name "Net-(R14-2)") (class "Default")
      (node (ref "Q5") (pin "G") (pinfunction "G_G") (pintype "passive"))
      (node (ref "R14") (pin "4") (pinfunction "2_4") (pintype "passive"))
      (node (ref "R15") (pin "3") (pinfunction "1_3") (pintype "passive"))
    )
    (net (code "45") (name "Net-(R30-2)") (class "Default")
      (node (ref "C24") (pin "1") (pinfunction "1_1") (pintype "passive"))
      (node (ref "R30") (pin "4") (pinfunction "2_4") (pintype "passive"))
    )
    (net (code "46") (name "Net-(U$1-(OC0A)PB2)") (class "Default")
      (node (ref "U$1") (pin "14") (pinfunction "(OC0A)PB2_14") (pintype "bidirectional"))
      (node (ref "U$7") (pin "3") (pinfunction "~{SD}_3") (pintype "bidirectional"))
    )
    (net (code "47") (name "Net-(U$1-(OC1A)PB3)") (class "Default")
      (node (ref "U$1") (pin "15") (pinfunction "(OC1A)PB3_15") (pintype "bidirectional"))
      (node (ref "U$7") (pin "2") (pinfunction "IN_2") (pintype "bidirectional"))
    )
    (net (code "48") (name "Net-(U$1-(RXD)PD0)") (class "Default")
      (node (ref "LED4") (pin "A") (pinfunction "A_A") (pintype "passive"))
      (node (ref "U$1") (pin "2") (pinfunction "(RXD)PD0_2") (pintype "bidirectional"))
    )
    (net (code "49") (name "Net-(U$1-(TXD)PD1)") (class "Default")
      (node (ref "LED3") (pin "A") (pinfunction "A_A") (pintype "passive"))
      (node (ref "U$1") (pin "3") (pinfunction "(TXD)PD1_3") (pintype "bidirectional"))
    )
    (net (code "50") (name "Net-(U$1-PA0(XTAL1))") (class "Default")
      (node (ref "C14") (pin "1") (pinfunction "1_1") (pintype "passive"))
      (node (ref "Q9") (pin "2") (pinfunction "2_2") (pintype "passive"))
      (node (ref "U$1") (pin "5") (pinfunction "PA0(XTAL1)_5") (pintype "bidirectional"))
    )
    (net (code "51") (name "Net-(U$1-PA1(XTAL2))") (class "Default")
      (node (ref "C15") (pin "1") (pinfunction "1_1") (pintype "passive"))
      (node (ref "Q9") (pin "1") (pinfunction "1_1") (pintype "passive"))
      (node (ref "U$1") (pin "4") (pinfunction "PA1(XTAL2)_4") (pintype "bidirectional"))
    )
    (net (code "52") (name "Net-(U$7-LO)") (class "Default")
      (node (ref "R3") (pin "1") (pinfunction "1_1") (pintype "passive"))
      (node (ref "U$7") (pin "5") (pinfunction "LO_5") (pintype "bidirectional"))
    )
    (net (code "53") (name "Net-(U$7-VB)") (class "Default")
      (node (ref "C4") (pin "1") (pinfunction "1_1") (pintype "passive"))
      (node (ref "D1") (pin "C") (pinfunction "C_C") (pintype "passive"))
      (node (ref "U$7") (pin "8") (pinfunction "VB_8") (pintype "bidirectional"))
    )
    (net (code "54") (name "unconnected-(U$1-(ICP)PD6-Pad11)") (class "Default")
      (node (ref "U$1") (pin "11") (pinfunction "(ICP)PD6_11") (pintype "bidirectional"))
    )
    (net (code "55") (name "unconnected-(U$1-PA2({slash}RESET)-Pad1)") (class "Default")
      (node (ref "U$1") (pin "1") (pinfunction "PA2(/RESET)_1") (pintype "input"))
    )
  )
)
